# Power.net
KiCad netlist of a schematic drawn in Altium Designer
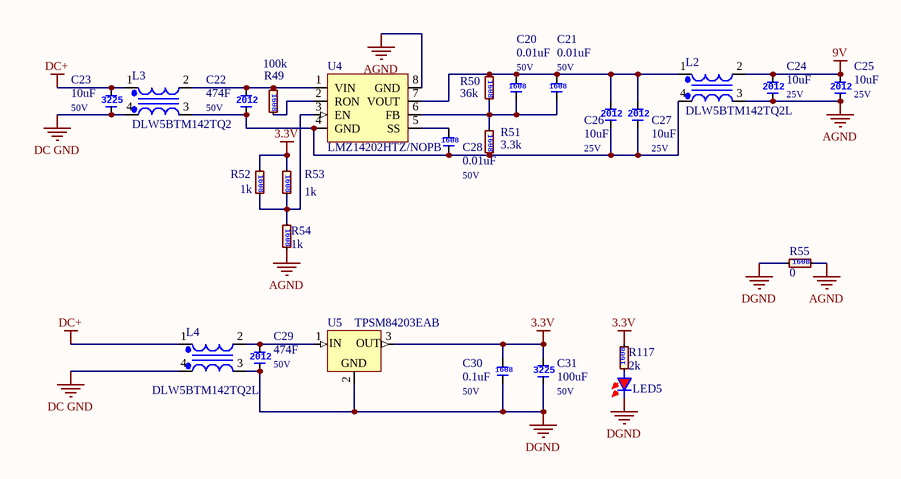
[diagram p0: Power.SchDoc]

(export (version "E")
  (design (tool "Eeschema 10.0.6"))
  (components
    (comp (ref "C20")
      (value "GCD188R71H103KA01D")
      (footprint "C1608")
      (description "セラコン1608サイズ")
      (fields (field (name "TAG") "0.01uF") (field (name "VOLTAGE") "50V"))
      (libsource (lib "Audio Prj") (part "C1608"))
    )
    (comp (ref "C21")
      (value "GCD188R71H103KA01D")
      (footprint "C1608")
      (description "セラコン1608サイズ")
      (fields (field (name "TAG") "0.01uF") (field (name "VOLTAGE") "50V"))
      (libsource (lib "Audio Prj") (part "C1608"))
    )
    (comp (ref "C22")
      (value "GRM21BR71H474MA88")
      (footprint "C2012")
      (description "セラコン2012サイズ")
      (fields (field (name "TAG") "474F") (field (name "VOLTAGE") "50V"))
      (libsource (lib "Audio Prj") (part "C2012"))
    )
    (comp (ref "C23")
      (value "UMK325C7106MM-T")
      (footprint "C3225")
      (description "セラコン3225サイズ")
      (fields (field (name "TAG") "10uF") (field (name "VOLTAGE") "50V"))
      (libsource (lib "Audio Prj") (part "C3225"))
    )
    (comp (ref "C24")
      (value "TMK212BBJ106MG-T")
      (footprint "C2012")
      (description "セラコン2012サイズ")
      (fields (field (name "TAG") "10uF") (field (name "VOLTAGE") "25V"))
      (libsource (lib "Audio Prj") (part "C2012"))
    )
    (comp (ref "C25")
      (value "TMK212BBJ106MG-T")
      (footprint "C2012")
      (description "セラコン2012サイズ")
      (fields (field (name "TAG") "10uF") (field (name "VOLTAGE") "25V"))
      (libsource (lib "Audio Prj") (part "C2012"))
    )
    (comp (ref "C26")
      (value "TMK212BBJ106MG-T")
      (footprint "C2012")
      (description "セラコン2012サイズ")
      (fields (field (name "TAG") "10uF") (field (name "VOLTAGE") "25V"))
      (libsource (lib "Audio Prj") (part "C2012"))
    )
    (comp (ref "C27")
      (value "TMK212BBJ106MG-T")
      (footprint "C2012")
      (description "セラコン2012サイズ")
      (fields (field (name "TAG") "10uF") (field (name "VOLTAGE") "25V"))
      (libsource (lib "Audio Prj") (part "C2012"))
    )
    (comp (ref "C28")
      (value "GCD188R71H103KA01D")
      (footprint "C1608")
      (description "セラコン1608サイズ")
      (fields (field (name "TAG") "0.01uF") (field (name "VOLTAGE") "50V"))
      (libsource (lib "Audio Prj") (part "C1608"))
    )
    (comp (ref "C29")
      (value "GRM21BR71H474MA88")
      (footprint "C2012")
      (description "セラコン2012サイズ")
      (fields (field (name "TAG") "474F") (field (name "VOLTAGE") "50V"))
      (libsource (lib "Audio Prj") (part "C2012"))
    )
    (comp (ref "C30")
      (value "CGA3E2X7R1H104K080AA")
      (footprint "C1608")
      (description "セラコン1608サイズ")
      (fields (field (name "TAG") "0.1uF") (field (name "VOLTAGE") "50V"))
      (libsource (lib "Audio Prj") (part "C1608"))
    )
    (comp (ref "C31")
      (value "EMK325ABJ107MM-T")
      (footprint "C3225")
      (description "セラコン3225サイズ")
      (fields (field (name "TAG") "100uF") (field (name "VOLTAGE") "50V"))
      (libsource (lib "Audio Prj") (part "C3225"))
    )
    (comp (ref "L2")
      (value "DLW5BTM142TQ2L")
      (footprint "DLW5BTM")
      (description "コモンモード,1A,4ピン")
      (libsource (lib "Audio Prj") (part "ACM3225"))
    )
    (comp (ref "L3")
      (value "DLW5BTM142TQ2")
      (footprint "DLW5BTM")
      (description "コモンモード,1A,4ピン")
      (libsource (lib "Audio Prj") (part "ACM3225"))
    )
    (comp (ref "L4")
      (value "DLW5BTM142TQ2L")
      (footprint "DLW5BTM")
      (description "コモンモード,1A,4ピン")
      (libsource (lib "Audio Prj") (part "ACM3225"))
    )
    (comp (ref "LED5")
      (value "APT1608LSECK/J4-PRV")
      (footprint "LED1608")
      (description "LED 1608 orange")
      (libsource (lib "Audio Prj") (part "LTST-C190CKT"))
    )
    (comp (ref "R49")
      (value "ERJ-PA3F1003V")
      (footprint "R1608")
      (description "厚膜チップ抵抗1608サイズ")
      (fields (field (name "TAG") "100k"))
      (libsource (lib "") (part "TF1608_1"))
    )
    (comp (ref "R50")
      (value "ERJ-PA3F3602V")
      (footprint "R1608")
      (description "厚膜チップ抵抗1608サイズ")
      (fields (field (name "TAG") "36k"))
      (libsource (lib "") (part "TF1608_1"))
    )
    (comp (ref "R51")
      (value "ERJ-PA3F3301V")
      (footprint "R1608")
      (description "厚膜チップ抵抗1608サイズ")
      (fields (field (name "TAG") "3.3k"))
      (libsource (lib "") (part "TF1608_1"))
    )
    (comp (ref "R52")
      (value "ERJ-PA3F1001V")
      (footprint "R1608")
      (description "厚膜チップ抵抗1608サイズ")
      (fields (field (name "TAG") "1k"))
      (libsource (lib "") (part "TF1608_1"))
    )
    (comp (ref "R53")
      (value "ERJ-PA3F1001V")
      (footprint "R1608")
      (description "厚膜チップ抵抗1608サイズ")
      (fields (field (name "TAG") "1k"))
      (libsource (lib "") (part "TF1608_1"))
    )
    (comp (ref "R54")
      (value "ERJ-PA3F1001V")
      (footprint "R1608")
      (description "厚膜チップ抵抗1608サイズ")
      (fields (field (name "TAG") "1k"))
      (libsource (lib "") (part "TF1608_1"))
    )
    (comp (ref "R55")
      (value "RK73Z1JTTD")
      (footprint "R1608")
      (description "厚膜チップ抵抗1608サイズ")
      (fields (field (name "TAG") "0"))
      (libsource (lib "") (part "TF1608_2"))
    )
    (comp (ref "R117")
      (value "ERJ-PA3F2001V")
      (footprint "R1608")
      (description "厚膜チップ抵抗1608サイズ")
      (fields (field (name "TAG") "2k"))
      (libsource (lib "Audio Prj") (part "TF1608"))
    )
    (comp (ref "U4")
      (value "LMZ14202HTZ/NOPB")
      (footprint "TO-PMOD-7")
      (description "DC DC CONVERTER 5-30V")
      (libsource (lib "Audio Prj") (part "LMZ14202HTZ/NOPB"))
    )
    (comp (ref "U5")
      (value "TPSM84203EAB")
      (footprint "TO220-3")
      (description "DC DC CONVERTER 3.3V")
      (libsource (lib "Audio Prj") (part "TPSM84203EAB"))
    )
  )
  (nets
    (net (code "1") (name "3.3V") (class "Default")
      (node (ref "C30") (pin "2") (pinfunction "2_2") (pintype "passive"))
      (node (ref "C31") (pin "2") (pinfunction "2_2") (pintype "passive"))
      (node (ref "R117") (pin "2") (pinfunction "2_2") (pintype "passive"))
      (node (ref "R52") (pin "1") (pinfunction "1_1") (pintype "passive"))
      (node (ref "R53") (pin "1") (pinfunction "1_1") (pintype "passive"))
      (node (ref "U5") (pin "3") (pinfunction "OUT_3") (pintype "output"))
    )
    (net (code "2") (name "9V") (class "Default")
      (node (ref "C24") (pin "2") (pinfunction "2_2") (pintype "passive"))
      (node (ref "C25") (pin "2") (pinfunction "2_2") (pintype "passive"))
      (node (ref "L2") (pin "2") (pinfunction "Pri+_2") (pintype "passive"))
    )
    (net (code "3") (name "AGND") (class "Default")
      (node (ref "C24") (pin "1") (pinfunction "1_1") (pintype "passive"))
      (node (ref "C25") (pin "1") (pinfunction "1_1") (pintype "passive"))
      (node (ref "L2") (pin "3") (pinfunction "Pri-_3") (pintype "passive"))
      (node (ref "R54") (pin "2") (pinfunction "2_2") (pintype "passive"))
      (node (ref "R55") (pin "2") (pinfunction "2_2") (pintype "passive"))
      (node (ref "U4") (pin "8") (pinfunction "GND_8") (pintype "power_in"))
    )
    (net (code "4") (name "DC GND") (class "Default")
      (node (ref "C23") (pin "1") (pinfunction "1_1") (pintype "passive"))
      (node (ref "L3") (pin "4") (pinfunction "Sec-_4") (pintype "passive"))
      (node (ref "L4") (pin "4") (pinfunction "Sec-_4") (pintype "passive"))
    )
    (net (code "5") (name "DC+") (class "Default")
      (node (ref "C23") (pin "2") (pinfunction "2_2") (pintype "passive"))
      (node (ref "L3") (pin "1") (pinfunction "Sec+_1") (pintype "passive"))
      (node (ref "L4") (pin "1") (pinfunction "Sec+_1") (pintype "passive"))
    )
    (net (code "6") (name "DGND") (class "Default")
      (node (ref "C29") (pin "1") (pinfunction "1_1") (pintype "passive"))
      (node (ref "C30") (pin "1") (pinfunction "1_1") (pintype "passive"))
      (node (ref "C31") (pin "1") (pinfunction "1_1") (pintype "passive"))
      (node (ref "L4") (pin "3") (pinfunction "Pri-_3") (pintype "passive"))
      (node (ref "LED5") (pin "K") (pinfunction "K_K") (pintype "passive"))
      (node (ref "R55") (pin "1") (pinfunction "1_1") (pintype "passive"))
      (node (ref "U5") (pin "2") (pinfunction "GND_2") (pintype "power_in"))
    )
    (net (code "7") (name "Net-(L2-Sec+)") (class "Default")
      (node (ref "C20") (pin "2") (pinfunction "2_2") (pintype "passive"))
      (node (ref "C21") (pin "2") (pinfunction "2_2") (pintype "passive"))
      (node (ref "C26") (pin "2") (pinfunction "2_2") (pintype "passive"))
      (node (ref "C27") (pin "2") (pinfunction "2_2") (pintype "passive"))
      (node (ref "L2") (pin "1") (pinfunction "Sec+_1") (pintype "passive"))
      (node (ref "R50") (pin "1") (pinfunction "1_1") (pintype "passive"))
      (node (ref "U4") (pin "7") (pinfunction "VOUT_7") (pintype "power_in"))
    )
    (net (code "8") (name "Net-(L2-Sec-)") (class "Default")
      (node (ref "C22") (pin "1") (pinfunction "1_1") (pintype "passive"))
      (node (ref "C26") (pin "1") (pinfunction "1_1") (pintype "passive"))
      (node (ref "C27") (pin "1") (pinfunction "1_1") (pintype "passive"))
      (node (ref "C28") (pin "1") (pinfunction "1_1") (pintype "passive"))
      (node (ref "L2") (pin "4") (pinfunction "Sec-_4") (pintype "passive"))
      (node (ref "L3") (pin "3") (pinfunction "Pri-_3") (pintype "passive"))
      (node (ref "R51") (pin "2") (pinfunction "2_2") (pintype "passive"))
      (node (ref "U4") (pin "4") (pinfunction "GND_4") (pintype "power_in"))
    )
    (net (code "9") (name "Net-(L3-Pri+)") (class "Default")
      (node (ref "C22") (pin "2") (pinfunction "2_2") (pintype "passive"))
      (node (ref "L3") (pin "2") (pinfunction "Pri+_2") (pintype "passive"))
      (node (ref "R49") (pin "1") (pinfunction "1_1") (pintype "passive"))
      (node (ref "U4") (pin "1") (pinfunction "VIN_1") (pintype "power_in"))
    )
    (net (code "10") (name "Net-(L4-Pri+)") (class "Default")
      (node (ref "C29") (pin "2") (pinfunction "2_2") (pintype "passive"))
      (node (ref "L4") (pin "2") (pinfunction "Pri+_2") (pintype "passive"))
      (node (ref "U5") (pin "1") (pinfunction "IN_1") (pintype "input"))
    )
    (net (code "11") (name "Net-(LED5-PadA)") (class "Default")
      (node (ref "LED5") (pin "A") (pinfunction "A_A") (pintype "passive"))
      (node (ref "R117") (pin "1") (pinfunction "1_1") (pintype "passive"))
    )
    (net (code "12") (name "Net-(U4-EN)") (class "Default")
      (node (ref "R52") (pin "2") (pinfunction "2_2") (pintype "passive"))
      (node (ref "R53") (pin "2") (pinfunction "2_2") (pintype "passive"))
      (node (ref "R54") (pin "1") (pinfunction "1_1") (pintype "passive"))
      (node (ref "U4") (pin "3") (pinfunction "EN_3") (pintype "input"))
    )
    (net (code "13") (name "Net-(U4-FB)") (class "Default")
      (node (ref "C20") (pin "1") (pinfunction "1_1") (pintype "passive"))
      (node (ref "C21") (pin "1") (pinfunction "1_1") (pintype "passive"))
      (node (ref "R50") (pin "2") (pinfunction "2_2") (pintype "passive"))
      (node (ref "R51") (pin "1") (pinfunction "1_1") (pintype "passive"))
      (node (ref "U4") (pin "6") (pinfunction "FB_6") (pintype "passive"))
    )
    (net (code "14") (name "Net-(U4-RON)") (class "Default")
      (node (ref "R49") (pin "2") (pinfunction "2_2") (pintype "passive"))
      (node (ref "U4") (pin "2") (pinfunction "RON_2") (pintype "passive"))
    )
    (net (code "15") (name "Net-(U4-SS)") (class "Default")
      (node (ref "C28") (pin "2") (pinfunction "2_2") (pintype "passive"))
      (node (ref "U4") (pin "5") (pinfunction "SS_5") (pintype "passive"))
    )
  )
)
